# 1-Schematic_Project_Stella.net
KiCad netlist of a schematic drawn in EasyEDA
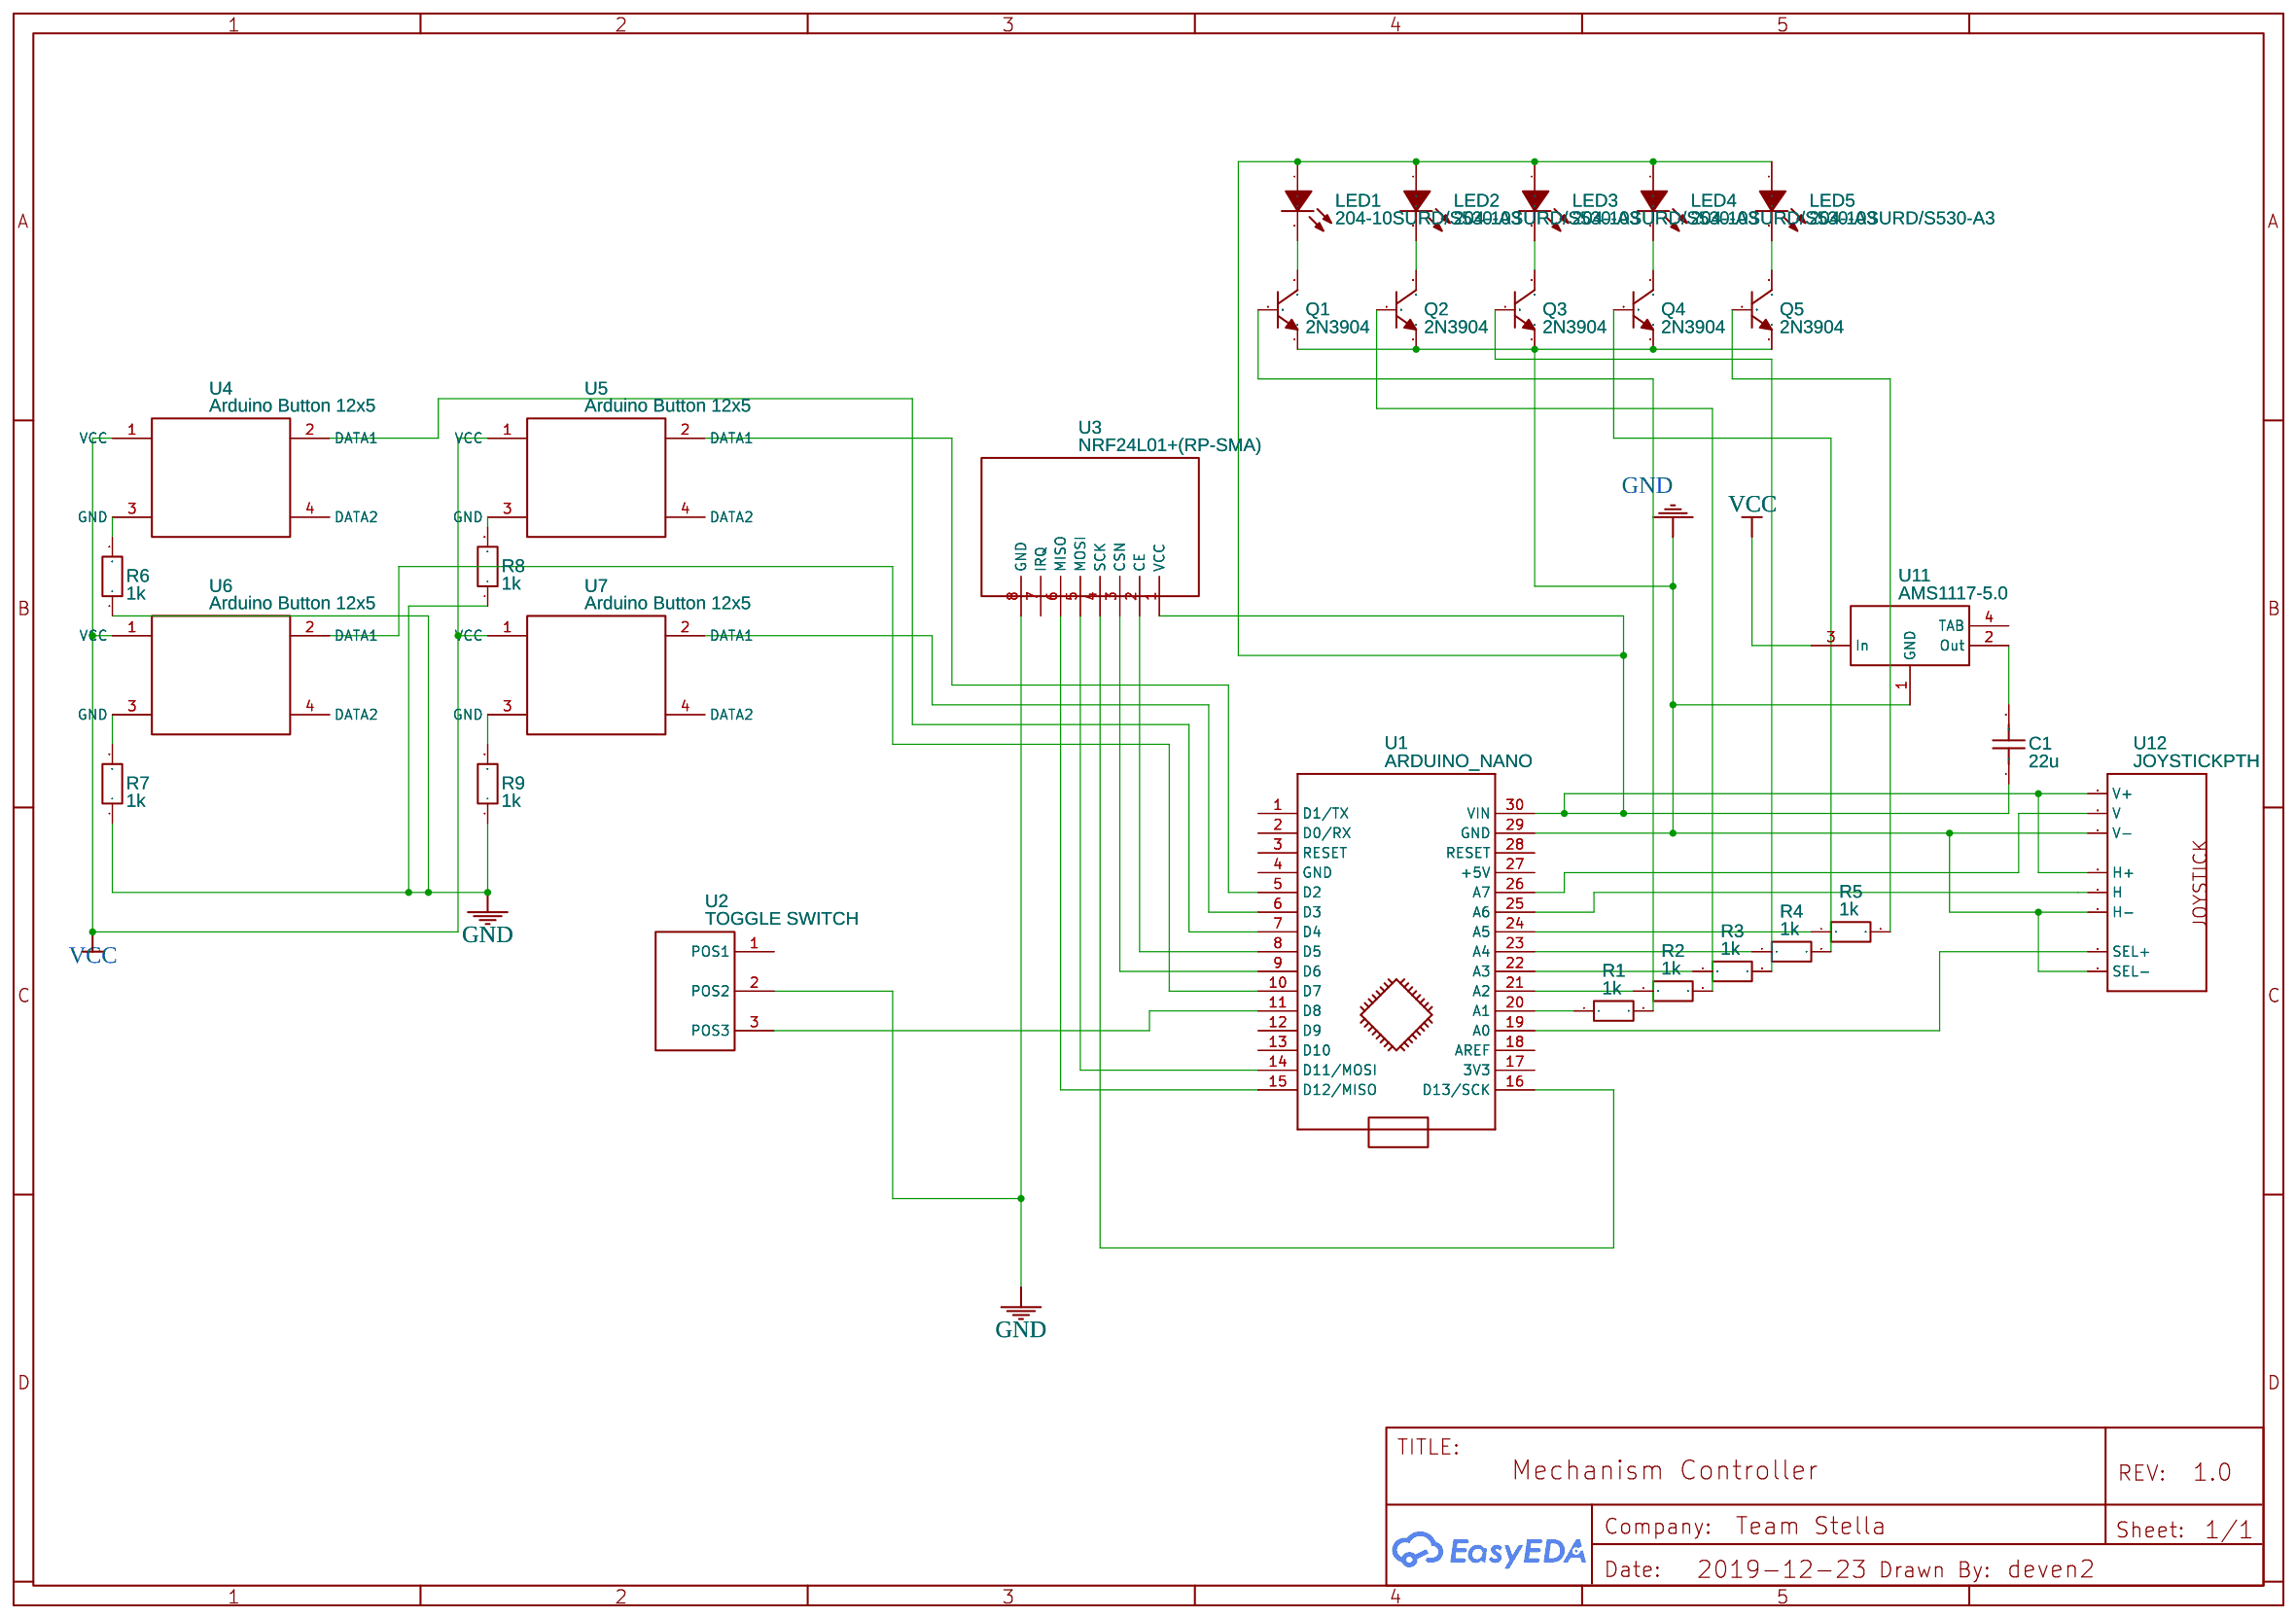
[diagram p0: schematic sheet]

(export (version "E")
  (design (tool "Eeschema 10.0.6"))
  (components
    (comp (ref "C1") (value "22u") (libsource (lib "") (part "Cap_RAD-0.1_US")))
    (comp (ref "LED1")
      (value "204-10SURD/S530-A3")
      (fields (field (name "BOM_Supplier Part") "C99772"))
      (libsource (lib "") (part "204-10SURD/S530-A3"))
    )
    (comp (ref "LED2")
      (value "204-10SURD/S530-A3")
      (fields (field (name "BOM_Supplier Part") "C99772"))
      (libsource (lib "") (part "204-10SURD/S530-A3"))
    )
    (comp (ref "LED3")
      (value "204-10SURD/S530-A3")
      (fields (field (name "BOM_Supplier Part") "C99772"))
      (libsource (lib "") (part "204-10SURD/S530-A3"))
    )
    (comp (ref "LED4")
      (value "204-10SURD/S530-A3")
      (fields (field (name "BOM_Supplier Part") "C99772"))
      (libsource (lib "") (part "204-10SURD/S530-A3"))
    )
    (comp (ref "LED5")
      (value "204-10SURD/S530-A3")
      (fields (field (name "BOM_Supplier Part") "C99772"))
      (libsource (lib "") (part "204-10SURD/S530-A3"))
    )
    (comp (ref "Q1")
      (value "2N3904")
      (fields (field (name "BOM_Supplier Part") "C118538"))
      (libsource (lib "") (part "2N3904"))
    )
    (comp (ref "Q2")
      (value "2N3904")
      (fields (field (name "BOM_Supplier Part") "C118538"))
      (libsource (lib "") (part "2N3904"))
    )
    (comp (ref "Q3")
      (value "2N3904")
      (fields (field (name "BOM_Supplier Part") "C118538"))
      (libsource (lib "") (part "2N3904"))
    )
    (comp (ref "Q4")
      (value "2N3904")
      (fields (field (name "BOM_Supplier Part") "C118538"))
      (libsource (lib "") (part "2N3904"))
    )
    (comp (ref "Q5")
      (value "2N3904")
      (fields (field (name "BOM_Supplier Part") "C118538"))
      (libsource (lib "") (part "2N3904"))
    )
    (comp (ref "R1") (value "1k") (libsource (lib "") (part "Res_AXIAL-0.3(1/8W)_EU")))
    (comp (ref "R2") (value "1k") (libsource (lib "") (part "Res_AXIAL-0.3(1/8W)_EU")))
    (comp (ref "R3") (value "1k") (libsource (lib "") (part "Res_AXIAL-0.3(1/8W)_EU")))
    (comp (ref "R4") (value "1k") (libsource (lib "") (part "Res_AXIAL-0.3(1/8W)_EU")))
    (comp (ref "R5") (value "1k") (libsource (lib "") (part "Res_AXIAL-0.3(1/8W)_EU")))
    (comp (ref "R6") (value "1k") (libsource (lib "") (part "Res_AXIAL-0.4(1/4W)_EU")))
    (comp (ref "R7") (value "1k") (libsource (lib "") (part "Res_AXIAL-0.4(1/4W)_EU")))
    (comp (ref "R8") (value "1k") (libsource (lib "") (part "Res_AXIAL-0.4(1/4W)_EU")))
    (comp (ref "R9") (value "1k") (libsource (lib "") (part "Res_AXIAL-0.4(1/4W)_EU")))
    (comp (ref "U1") (value "ARDUINO_NANO") (libsource (lib "") (part "Unknown_700_480")))
    (comp (ref "U2") (value "TOGGLE SWITCH") (libsource (lib "") (part "TOGGLE SWITCH")))
    (comp (ref "U3") (value "NRF24L01+(RP-SMA)") (libsource (lib "") (part "Unknown_520_265")))
    (comp (ref "U4") (value "Arduino Button 12x5") (libsource (lib "") (part "Unknown_70_215")))
    (comp (ref "U5") (value "Arduino Button 12x5") (libsource (lib "") (part "Unknown_260_215")))
    (comp (ref "U6") (value "Arduino Button 12x5") (libsource (lib "") (part "Unknown_70_315")))
    (comp (ref "U7") (value "Arduino Button 12x5") (libsource (lib "") (part "Unknown_260_315")))
    (comp (ref "U11")
      (value "AMS1117-5.0")
      (fields (field (name "BOM_Supplier Part") "C6187"))
      (libsource (lib "") (part "Unknown_960_325"))
    )
    (comp (ref "U12") (value "JOYSTICKPTH") (libsource (lib "") (part "JOYSTICKPTH")))
  )
  (nets
    (net (code "1") (name "GND") (class "Default")
      (node (ref "Q1") (pin "1") (pinfunction "E_1") (pintype "unspecified"))
      (node (ref "Q2") (pin "1") (pinfunction "E_1") (pintype "unspecified"))
      (node (ref "Q3") (pin "1") (pinfunction "E_1") (pintype "unspecified"))
      (node (ref "Q4") (pin "1") (pinfunction "E_1") (pintype "unspecified"))
      (node (ref "Q5") (pin "1") (pinfunction "E_1") (pintype "unspecified"))
      (node (ref "R6") (pin "1") (pinfunction "1_1") (pintype "unspecified"))
      (node (ref "R7") (pin "1") (pinfunction "1_1") (pintype "unspecified"))
      (node (ref "R8") (pin "1") (pinfunction "1_1") (pintype "unspecified"))
      (node (ref "R9") (pin "1") (pinfunction "1_1") (pintype "unspecified"))
      (node (ref "U1") (pin "29") (pinfunction "GND_29") (pintype "unspecified"))
      (node (ref "U11") (pin "1") (pinfunction "GND_1") (pintype "unspecified"))
      (node (ref "U12") (pin "B2A") (pinfunction "SEL-_B2A") (pintype "unspecified"))
      (node (ref "U12") (pin "H3") (pinfunction "H-_H3") (pintype "unspecified"))
      (node (ref "U12") (pin "V3") (pinfunction "V-_V3") (pintype "unspecified"))
      (node (ref "U2") (pin "2") (pinfunction "POS2_2") (pintype "unspecified"))
      (node (ref "U3") (pin "8") (pinfunction "GND_8") (pintype "unspecified"))
    )
    (net (code "2") (name "Net-(LED1-A)") (class "Default")
      (node (ref "C1") (pin "1") (pinfunction "1_1") (pintype "unspecified"))
      (node (ref "LED1") (pin "1") (pinfunction "A_1") (pintype "unspecified"))
      (node (ref "LED2") (pin "1") (pinfunction "A_1") (pintype "unspecified"))
      (node (ref "LED3") (pin "1") (pinfunction "A_1") (pintype "unspecified"))
      (node (ref "LED4") (pin "1") (pinfunction "A_1") (pintype "unspecified"))
      (node (ref "LED5") (pin "1") (pinfunction "A_1") (pintype "unspecified"))
      (node (ref "U1") (pin "30") (pinfunction "VIN_30") (pintype "unspecified"))
      (node (ref "U12") (pin "H1") (pinfunction "H+_H1") (pintype "unspecified"))
      (node (ref "U12") (pin "V1") (pinfunction "V+_V1") (pintype "unspecified"))
      (node (ref "U3") (pin "1") (pinfunction "VCC_1") (pintype "unspecified"))
    )
    (net (code "3") (name "Net-(LED1-K)") (class "Default")
      (node (ref "LED1") (pin "2") (pinfunction "K_2") (pintype "unspecified"))
      (node (ref "Q1") (pin "3") (pinfunction "C_3") (pintype "unspecified"))
    )
    (net (code "4") (name "Net-(LED2-K)") (class "Default")
      (node (ref "LED2") (pin "2") (pinfunction "K_2") (pintype "unspecified"))
      (node (ref "Q2") (pin "3") (pinfunction "C_3") (pintype "unspecified"))
    )
    (net (code "5") (name "Net-(LED3-K)") (class "Default")
      (node (ref "LED3") (pin "2") (pinfunction "K_2") (pintype "unspecified"))
      (node (ref "Q3") (pin "3") (pinfunction "C_3") (pintype "unspecified"))
    )
    (net (code "6") (name "Net-(LED4-K)") (class "Default")
      (node (ref "LED4") (pin "2") (pinfunction "K_2") (pintype "unspecified"))
      (node (ref "Q4") (pin "3") (pinfunction "C_3") (pintype "unspecified"))
    )
    (net (code "7") (name "Net-(LED5-K)") (class "Default")
      (node (ref "LED5") (pin "2") (pinfunction "K_2") (pintype "unspecified"))
      (node (ref "Q5") (pin "3") (pinfunction "C_3") (pintype "unspecified"))
    )
    (net (code "8") (name "Net-(Q1-B)") (class "Default")
      (node (ref "Q1") (pin "2") (pinfunction "B_2") (pintype "unspecified"))
      (node (ref "R1") (pin "2") (pinfunction "2_2") (pintype "unspecified"))
    )
    (net (code "9") (name "Net-(Q2-B)") (class "Default")
      (node (ref "Q2") (pin "2") (pinfunction "B_2") (pintype "unspecified"))
      (node (ref "R2") (pin "2") (pinfunction "2_2") (pintype "unspecified"))
    )
    (net (code "10") (name "Net-(Q3-B)") (class "Default")
      (node (ref "Q3") (pin "2") (pinfunction "B_2") (pintype "unspecified"))
      (node (ref "R3") (pin "2") (pinfunction "2_2") (pintype "unspecified"))
    )
    (net (code "11") (name "Net-(Q4-B)") (class "Default")
      (node (ref "Q4") (pin "2") (pinfunction "B_2") (pintype "unspecified"))
      (node (ref "R4") (pin "2") (pinfunction "2_2") (pintype "unspecified"))
    )
    (net (code "12") (name "Net-(Q5-B)") (class "Default")
      (node (ref "Q5") (pin "2") (pinfunction "B_2") (pintype "unspecified"))
      (node (ref "R5") (pin "2") (pinfunction "2_2") (pintype "unspecified"))
    )
    (net (code "13") (name "Net-(U1-A0)") (class "Default")
      (node (ref "U1") (pin "19") (pinfunction "A0_19") (pintype "unspecified"))
      (node (ref "U12") (pin "B1A") (pinfunction "SEL+_B1A") (pintype "unspecified"))
    )
    (net (code "14") (name "Net-(U1-A1)") (class "Default")
      (node (ref "R1") (pin "1") (pinfunction "1_1") (pintype "unspecified"))
      (node (ref "U1") (pin "20") (pinfunction "A1_20") (pintype "unspecified"))
    )
    (net (code "15") (name "Net-(U1-A2)") (class "Default")
      (node (ref "R2") (pin "1") (pinfunction "1_1") (pintype "unspecified"))
      (node (ref "U1") (pin "21") (pinfunction "A2_21") (pintype "unspecified"))
    )
    (net (code "16") (name "Net-(U1-A3)") (class "Default")
      (node (ref "R3") (pin "1") (pinfunction "1_1") (pintype "unspecified"))
      (node (ref "U1") (pin "22") (pinfunction "A3_22") (pintype "unspecified"))
    )
    (net (code "17") (name "Net-(U1-A4)") (class "Default")
      (node (ref "R4") (pin "1") (pinfunction "1_1") (pintype "unspecified"))
      (node (ref "U1") (pin "23") (pinfunction "A4_23") (pintype "unspecified"))
    )
    (net (code "18") (name "Net-(U1-A5)") (class "Default")
      (node (ref "R5") (pin "1") (pinfunction "1_1") (pintype "unspecified"))
      (node (ref "U1") (pin "24") (pinfunction "A5_24") (pintype "unspecified"))
    )
    (net (code "19") (name "Net-(U1-A6)") (class "Default")
      (node (ref "U1") (pin "25") (pinfunction "A6_25") (pintype "unspecified"))
      (node (ref "U12") (pin "H2") (pinfunction "H_H2") (pintype "unspecified"))
    )
    (net (code "20") (name "Net-(U1-A7)") (class "Default")
      (node (ref "U1") (pin "26") (pinfunction "A7_26") (pintype "unspecified"))
      (node (ref "U12") (pin "V2") (pinfunction "V_V2") (pintype "unspecified"))
    )
    (net (code "21") (name "Net-(U1-D2)") (class "Default")
      (node (ref "U1") (pin "5") (pinfunction "D2_5") (pintype "unspecified"))
      (node (ref "U5") (pin "2") (pinfunction "DATA1_2") (pintype "unspecified"))
    )
    (net (code "22") (name "Net-(U1-D3)") (class "Default")
      (node (ref "U1") (pin "6") (pinfunction "D3_6") (pintype "unspecified"))
      (node (ref "U7") (pin "2") (pinfunction "DATA1_2") (pintype "unspecified"))
    )
    (net (code "23") (name "Net-(U1-D4)") (class "Default")
      (node (ref "U1") (pin "7") (pinfunction "D4_7") (pintype "unspecified"))
      (node (ref "U4") (pin "2") (pinfunction "DATA1_2") (pintype "unspecified"))
    )
    (net (code "24") (name "Net-(U1-D5)") (class "Default")
      (node (ref "U1") (pin "8") (pinfunction "D5_8") (pintype "unspecified"))
      (node (ref "U3") (pin "2") (pinfunction "CE_2") (pintype "unspecified"))
    )
    (net (code "25") (name "Net-(U1-D6)") (class "Default")
      (node (ref "U1") (pin "9") (pinfunction "D6_9") (pintype "unspecified"))
      (node (ref "U3") (pin "3") (pinfunction "CSN_3") (pintype "unspecified"))
    )
    (net (code "26") (name "Net-(U1-D7)") (class "Default")
      (node (ref "U1") (pin "10") (pinfunction "D7_10") (pintype "unspecified"))
      (node (ref "U6") (pin "2") (pinfunction "DATA1_2") (pintype "unspecified"))
    )
    (net (code "27") (name "Net-(U1-D8)") (class "Default")
      (node (ref "U1") (pin "11") (pinfunction "D8_11") (pintype "unspecified"))
      (node (ref "U2") (pin "3") (pinfunction "POS3_3") (pintype "unspecified"))
    )
    (net (code "28") (name "Net-(U1-D11{slash}MOSI)") (class "Default")
      (node (ref "U1") (pin "14") (pinfunction "D11/MOSI_14") (pintype "unspecified"))
      (node (ref "U3") (pin "5") (pinfunction "MOSI_5") (pintype "unspecified"))
    )
    (net (code "29") (name "Net-(U1-D12{slash}MISO)") (class "Default")
      (node (ref "U1") (pin "15") (pinfunction "D12/MISO_15") (pintype "unspecified"))
      (node (ref "U3") (pin "6") (pinfunction "MISO_6") (pintype "unspecified"))
    )
    (net (code "30") (name "Net-(U1-D13{slash}SCK)") (class "Default")
      (node (ref "U1") (pin "16") (pinfunction "D13/SCK_16") (pintype "unspecified"))
      (node (ref "U3") (pin "4") (pinfunction "SCK_4") (pintype "unspecified"))
    )
    (net (code "31") (name "Net-(U4-GND)") (class "Default")
      (node (ref "R6") (pin "2") (pinfunction "2_2") (pintype "unspecified"))
      (node (ref "U4") (pin "3") (pinfunction "GND_3") (pintype "unspecified"))
    )
    (net (code "32") (name "Net-(U5-GND)") (class "Default")
      (node (ref "R8") (pin "2") (pinfunction "2_2") (pintype "unspecified"))
      (node (ref "U5") (pin "3") (pinfunction "GND_3") (pintype "unspecified"))
    )
    (net (code "33") (name "Net-(U6-GND)") (class "Default")
      (node (ref "R7") (pin "2") (pinfunction "2_2") (pintype "unspecified"))
      (node (ref "U6") (pin "3") (pinfunction "GND_3") (pintype "unspecified"))
    )
    (net (code "34") (name "Net-(U7-GND)") (class "Default")
      (node (ref "R9") (pin "2") (pinfunction "2_2") (pintype "unspecified"))
      (node (ref "U7") (pin "3") (pinfunction "GND_3") (pintype "unspecified"))
    )
    (net (code "35") (name "Net-(U11-Out)") (class "Default")
      (node (ref "C1") (pin "2") (pinfunction "2_2") (pintype "unspecified"))
      (node (ref "U11") (pin "2") (pinfunction "Out_2") (pintype "unspecified"))
    )
    (net (code "36") (name "VCC") (class "Default")
      (node (ref "U11") (pin "3") (pinfunction "In_3") (pintype "unspecified"))
      (node (ref "U4") (pin "1") (pinfunction "VCC_1") (pintype "unspecified"))
      (node (ref "U5") (pin "1") (pinfunction "VCC_1") (pintype "unspecified"))
      (node (ref "U6") (pin "1") (pinfunction "VCC_1") (pintype "unspecified"))
      (node (ref "U7") (pin "1") (pinfunction "VCC_1") (pintype "unspecified"))
    )
    (net (code "37") (name "unconnected-(U1-+5V-Pad27)") (class "Default")
      (node (ref "U1") (pin "27") (pinfunction "+5V_27") (pintype "unspecified"))
    )
    (net (code "38") (name "unconnected-(U1-3V3-Pad17)") (class "Default")
      (node (ref "U1") (pin "17") (pinfunction "3V3_17") (pintype "unspecified"))
    )
    (net (code "39") (name "unconnected-(U1-AREF-Pad18)") (class "Default")
      (node (ref "U1") (pin "18") (pinfunction "AREF_18") (pintype "unspecified"))
    )
    (net (code "40") (name "unconnected-(U1-D0{slash}RX-Pad2)") (class "Default")
      (node (ref "U1") (pin "2") (pinfunction "D0/RX_2") (pintype "unspecified"))
    )
    (net (code "41") (name "unconnected-(U1-D1{slash}TX-Pad1)") (class "Default")
      (node (ref "U1") (pin "1") (pinfunction "D1/TX_1") (pintype "unspecified"))
    )
    (net (code "42") (name "unconnected-(U1-D9-Pad12)") (class "Default")
      (node (ref "U1") (pin "12") (pinfunction "D9_12") (pintype "unspecified"))
    )
    (net (code "43") (name "unconnected-(U1-D10-Pad13)") (class "Default")
      (node (ref "U1") (pin "13") (pinfunction "D10_13") (pintype "unspecified"))
    )
    (net (code "44") (name "unconnected-(U1-GND-Pad4)") (class "Default")
      (node (ref "U1") (pin "4") (pinfunction "GND_4") (pintype "unspecified"))
    )
    (net (code "45") (name "unconnected-(U1-RESET-Pad3)") (class "Default")
      (node (ref "U1") (pin "3") (pinfunction "RESET_3") (pintype "unspecified"))
    )
    (net (code "46") (name "unconnected-(U1-RESET-Pad28)") (class "Default")
      (node (ref "U1") (pin "28") (pinfunction "RESET_28") (pintype "unspecified"))
    )
    (net (code "47") (name "unconnected-(U2-POS1-Pad1)") (class "Default")
      (node (ref "U2") (pin "1") (pinfunction "POS1_1") (pintype "unspecified"))
    )
    (net (code "48") (name "unconnected-(U3-IRQ-Pad7)") (class "Default")
      (node (ref "U3") (pin "7") (pinfunction "IRQ_7") (pintype "unspecified"))
    )
    (net (code "49") (name "unconnected-(U4-DATA2-Pad4)") (class "Default")
      (node (ref "U4") (pin "4") (pinfunction "DATA2_4") (pintype "unspecified"))
    )
    (net (code "50") (name "unconnected-(U5-DATA2-Pad4)") (class "Default")
      (node (ref "U5") (pin "4") (pinfunction "DATA2_4") (pintype "unspecified"))
    )
    (net (code "51") (name "unconnected-(U6-DATA2-Pad4)") (class "Default")
      (node (ref "U6") (pin "4") (pinfunction "DATA2_4") (pintype "unspecified"))
    )
    (net (code "52") (name "unconnected-(U7-DATA2-Pad4)") (class "Default")
      (node (ref "U7") (pin "4") (pinfunction "DATA2_4") (pintype "unspecified"))
    )
    (net (code "53") (name "unconnected-(U11-TAB-Pad4)") (class "Default")
      (node (ref "U11") (pin "4") (pinfunction "TAB_4") (pintype "unspecified"))
    )
  )
)
